# Handy_sense_v_1_0_0.net
KiCad netlist of a schematic drawn in EAGLE
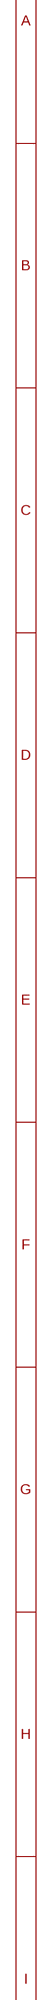
[diagram p0: schematic, sheet 1, part 1 of 2]
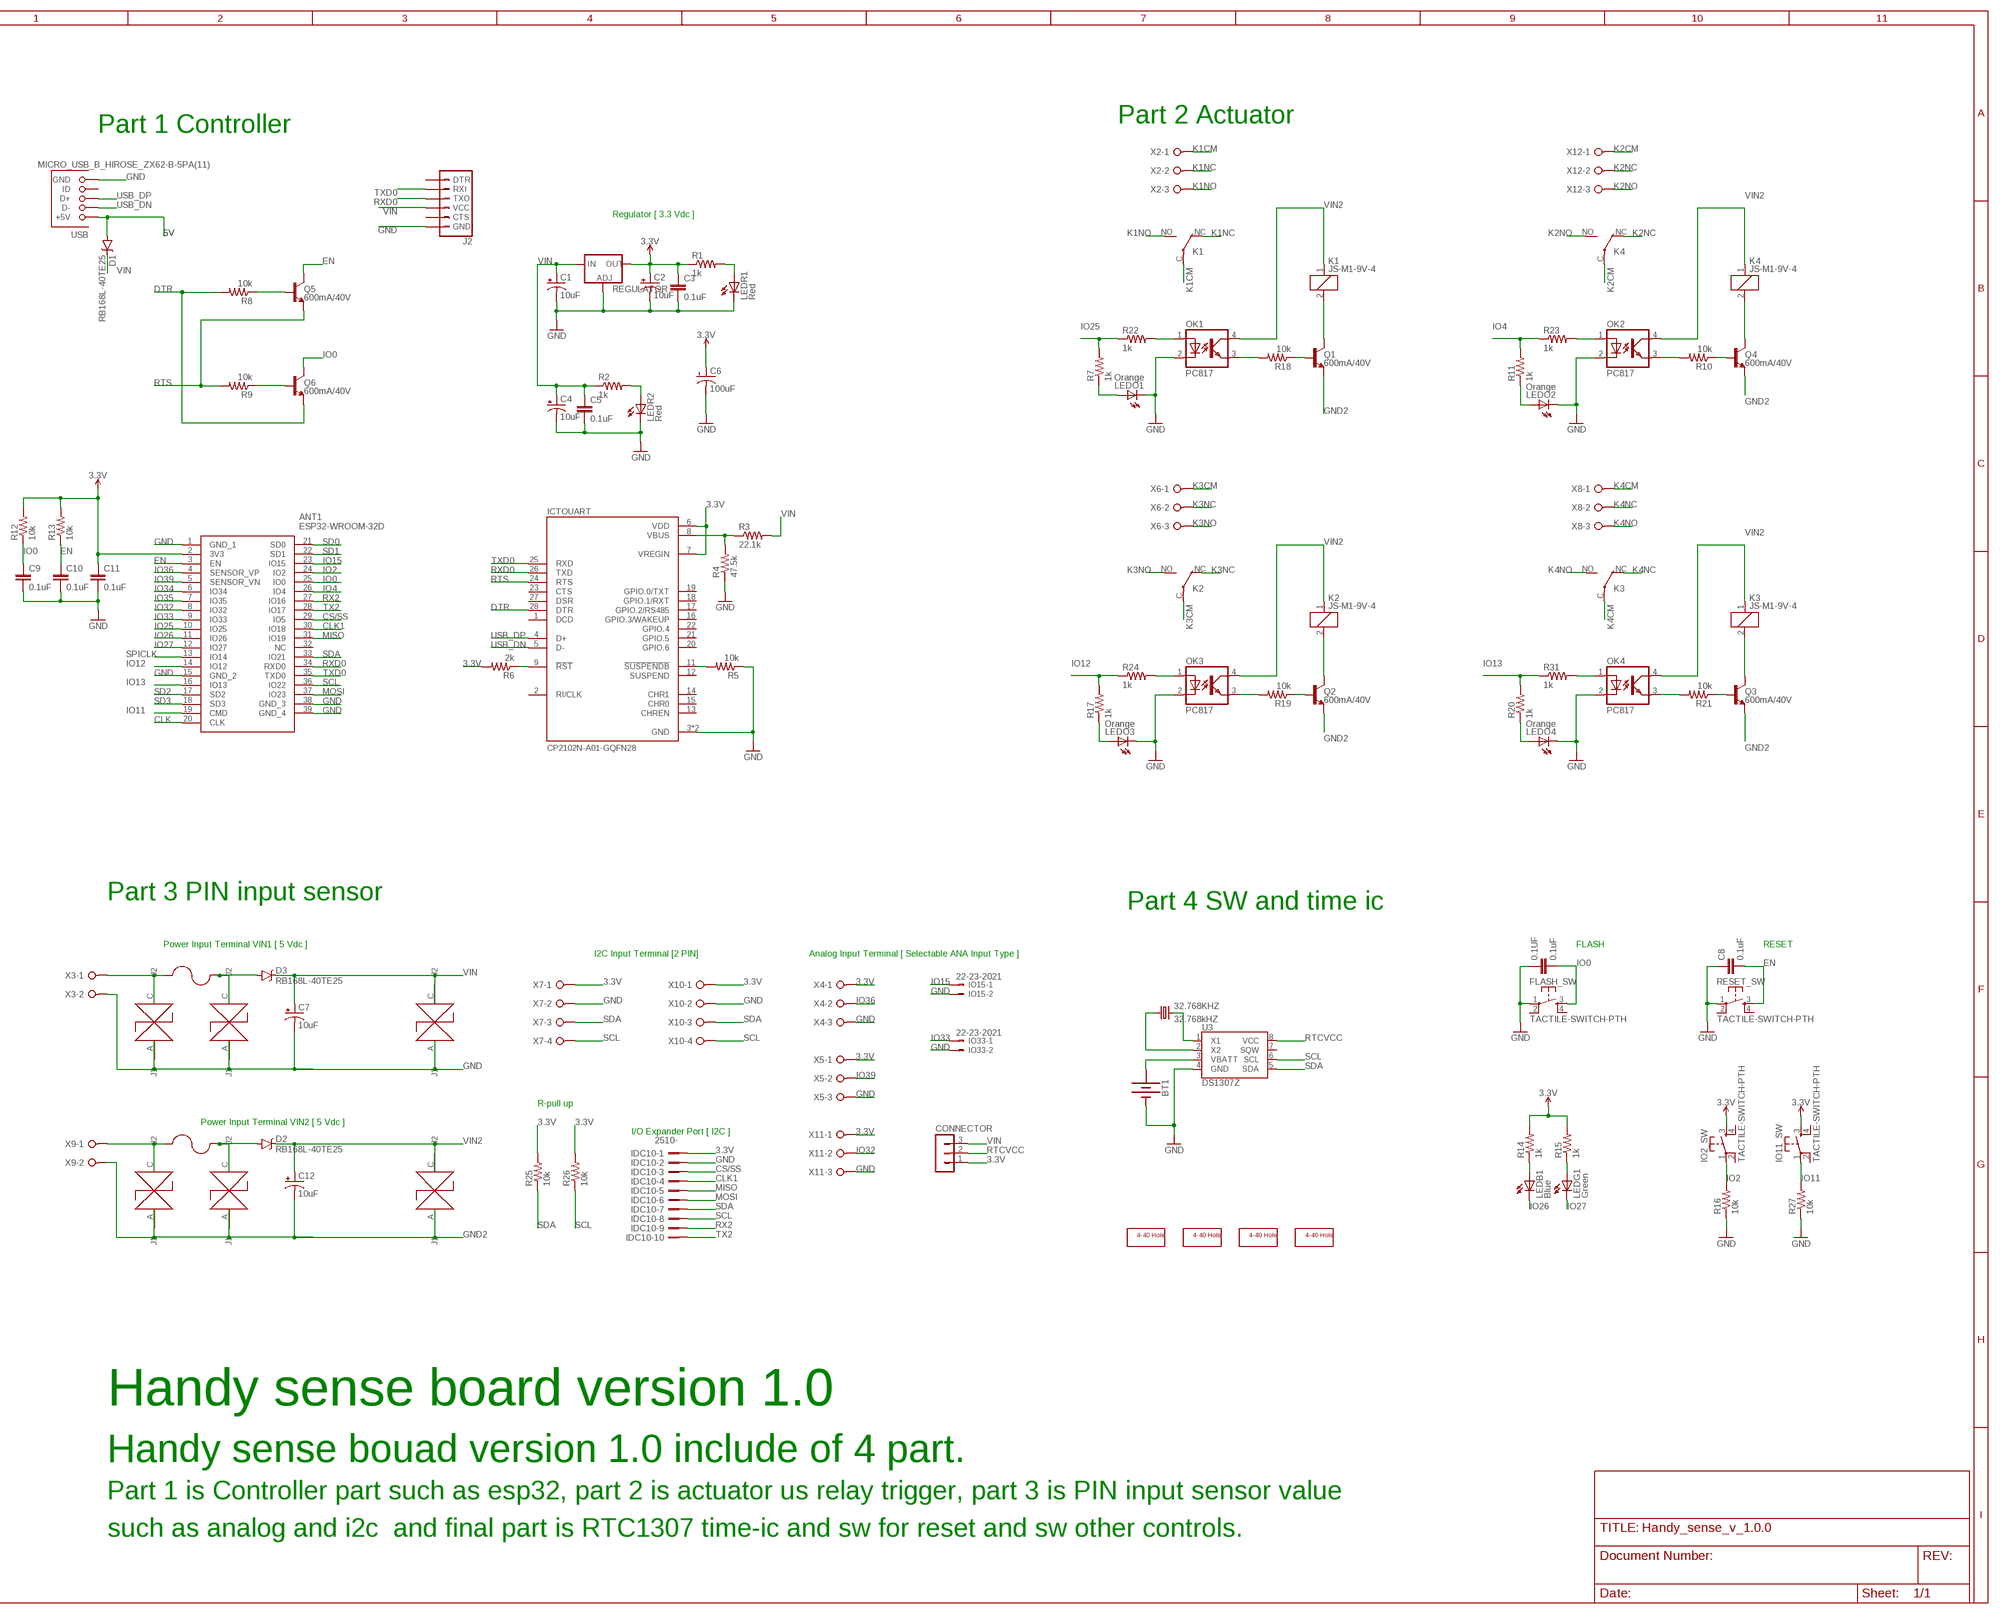
[diagram p1: schematic, sheet 1, part 2 of 2]

(export (version "E")
  (design (tool "Eeschema 10.0.6"))
  (components
    (comp (ref "0.1UF")
      (value "0.1uF")
      (footprint "eagle-import:0805")
      (libsource (lib "eagle-import") (part "CAP0805"))
    )
    (comp (ref "32.768KHZ")
      (value "32.768kHZ")
      (footprint "eagle-import:TC26H")
      (libsource (lib "eagle-import") (part "CRYSTALTC26H"))
    )
    (comp (ref "ANT1")
      (value "ESP32-WROOM-32D")
      (footprint "eagle-import:ESP32WROOM32D")
      (fields (field (name "MOUSER_PART_NUMBER") "356-ESP32WROOM-32D"))
      (libsource (lib "eagle-import") (part "ESP32-WROOM-32D"))
    )
    (comp (ref "BT1")
      (value "BATTERY-20MM_PTH_KIT")
      (footprint "eagle-import:BATTCOM_20MM_PTH_KIT")
      (libsource (lib "eagle-import") (part "BATTERY-20MM_PTH_KIT"))
    )
    (comp (ref "C1")
      (value "10uF")
      (footprint "eagle-import:EIA3216")
      (libsource (lib "eagle-import") (part "10UF-16V-10%(TANT)"))
    )
    (comp (ref "C2")
      (value "10uF")
      (footprint "eagle-import:EIA3216")
      (libsource (lib "eagle-import") (part "10UF-16V-10%(TANT)"))
    )
    (comp (ref "C3")
      (value "0.1uF")
      (footprint "eagle-import:0805")
      (libsource (lib "eagle-import") (part "CAP0805"))
    )
    (comp (ref "C4")
      (value "10uF")
      (footprint "eagle-import:EIA3216")
      (libsource (lib "eagle-import") (part "10UF-16V-10%(TANT)"))
    )
    (comp (ref "C5")
      (value "0.1uF")
      (footprint "eagle-import:0805")
      (libsource (lib "eagle-import") (part "CAP0805"))
    )
    (comp (ref "C6")
      (value "100uF")
      (footprint "eagle-import:EIA7343")
      (libsource (lib "eagle-import") (part "100UF-POLAR-EIA7343-16V-10%(TANT)"))
    )
    (comp (ref "C7")
      (value "10uF")
      (footprint "eagle-import:EIA3216")
      (libsource (lib "eagle-import") (part "10UF-16V-10%(TANT)"))
    )
    (comp (ref "C8")
      (value "0.1uF")
      (footprint "eagle-import:0805")
      (libsource (lib "eagle-import") (part "CAP0805"))
    )
    (comp (ref "C9")
      (value "0.1uF")
      (footprint "eagle-import:0805")
      (libsource (lib "eagle-import") (part "CAP0805"))
    )
    (comp (ref "C10")
      (value "0.1uF")
      (footprint "eagle-import:0805")
      (libsource (lib "eagle-import") (part "CAP0805"))
    )
    (comp (ref "C11")
      (value "0.1uF")
      (footprint "eagle-import:0805")
      (libsource (lib "eagle-import") (part "CAP0805"))
    )
    (comp (ref "C12")
      (value "10uF")
      (footprint "eagle-import:EIA3216")
      (libsource (lib "eagle-import") (part "10UF-16V-10%(TANT)"))
    )
    (comp (ref "CONNECTOR")
      (value "MA03-1")
      (footprint "eagle-import:MA03-1")
      (libsource (lib "eagle-import") (part "MA03-1"))
    )
    (comp (ref "D1")
      (value "RB168L-40TE25")
      (footprint "eagle-import:SMA-DIODE")
      (libsource (lib "eagle-import") (part "DIODE-SCHOTTKY-MBRA140"))
    )
    (comp (ref "D2")
      (value "RB168L-40TE25")
      (footprint "eagle-import:SMA-DIODE")
      (libsource (lib "eagle-import") (part "DIODE-SCHOTTKY-MBRA140"))
    )
    (comp (ref "D3")
      (value "RB168L-40TE25")
      (footprint "eagle-import:SMA-DIODE")
      (libsource (lib "eagle-import") (part "DIODE-SCHOTTKY-MBRA140"))
    )
    (comp (ref "FLASH_SW")
      (value "TACTILE-SWITCH-PTH")
      (footprint "eagle-import:TAC-SWITCH-PTH")
      (libsource (lib "eagle-import") (part "TACTILE-SWITCH-PTH"))
    )
    (comp (ref "HOLE0")
      (value "SCREW_HOLE_4-40")
      (footprint "eagle-import:SCREW_HOLE_4-40")
      (libsource (lib "eagle-import") (part "SCREW_HOLE_4-40"))
    )
    (comp (ref "HOLE1")
      (value "SCREW_HOLE_4-40")
      (footprint "eagle-import:SCREW_HOLE_4-40")
      (libsource (lib "eagle-import") (part "SCREW_HOLE_4-40"))
    )
    (comp (ref "HOLE2")
      (value "SCREW_HOLE_4-40")
      (footprint "eagle-import:SCREW_HOLE_4-40")
      (libsource (lib "eagle-import") (part "SCREW_HOLE_4-40"))
    )
    (comp (ref "HOLE3")
      (value "SCREW_HOLE_4-40")
      (footprint "eagle-import:SCREW_HOLE_4-40")
      (libsource (lib "eagle-import") (part "SCREW_HOLE_4-40"))
    )
    (comp (ref "ICTOUART")
      (value "CP2102N-A01-GQFN28")
      (footprint "eagle-import:QFN50P500X500X80-29N")
      (fields (field (name "MF") "Silicon Labs"))
      (libsource (lib "eagle-import") (part "CP2102N-A01-GQFN28"))
    )
    (comp (ref "IDC10")
      (value "2510-")
      (footprint "eagle-import:PAK100_2500-10")
      (fields (field (name "MF") "3M") (field (name "MPN") "2510-6002UB"))
      (libsource (lib "eagle-import") (part "2510-"))
    )
    (comp (ref "IO2_SW")
      (value "TACTILE-SWITCH-PTH")
      (footprint "eagle-import:TAC-SWITCH-PTH")
      (libsource (lib "eagle-import") (part "TACTILE-SWITCH-PTH"))
    )
    (comp (ref "IO11_SW")
      (value "TACTILE-SWITCH-PTH")
      (footprint "eagle-import:TAC-SWITCH-PTH")
      (libsource (lib "eagle-import") (part "TACTILE-SWITCH-PTH"))
    )
    (comp (ref "IO15")
      (value "22-23-2021")
      (footprint "eagle-import:22-23-2021")
      (fields (field (name "MF") "MOLEX"))
      (libsource (lib "eagle-import") (part "22-23-2021"))
    )
    (comp (ref "IO33")
      (value "22-23-2021")
      (footprint "eagle-import:22-23-2021")
      (fields (field (name "MF") "MOLEX"))
      (libsource (lib "eagle-import") (part "22-23-2021"))
    )
    (comp (ref "J2")
      (value "6_PIN_SERIAL_TARGET_SILK")
      (footprint "eagle-import:1X06")
      (libsource (lib "eagle-import") (part "6_PIN_SERIAL_TARGET_SILK"))
    )
    (comp (ref "J28CA1")
      (value "SMBJ28CA")
      (footprint "eagle-import:DIOM505270X240")
      (libsource (lib "eagle-import") (part "SMBJ28CA"))
    )
    (comp (ref "J28CA2")
      (value "SMBJ28CA")
      (footprint "eagle-import:DIOM505270X240")
      (libsource (lib "eagle-import") (part "SMBJ28CA"))
    )
    (comp (ref "J28CA3")
      (value "SMBJ28CA")
      (footprint "eagle-import:DIOM505270X240")
      (libsource (lib "eagle-import") (part "SMBJ28CA"))
    )
    (comp (ref "J28CA4")
      (value "SMBJ28CA")
      (footprint "eagle-import:DIOM505270X240")
      (libsource (lib "eagle-import") (part "SMBJ28CA"))
    )
    (comp (ref "J28CA5")
      (value "SMBJ28CA")
      (footprint "eagle-import:DIOM505270X240")
      (libsource (lib "eagle-import") (part "SMBJ28CA"))
    )
    (comp (ref "J28CA6")
      (value "SMBJ28CA")
      (footprint "eagle-import:DIOM505270X240")
      (libsource (lib "eagle-import") (part "SMBJ28CA"))
    )
    (comp (ref "K1")
      (value "JS-M1-9V-4")
      (footprint "eagle-import:JS-M")
      (libsource (lib "eagle-import") (part "JS-M1-9V-4"))
    )
    (comp (ref "K2")
      (value "JS-M1-9V-4")
      (footprint "eagle-import:JS-M")
      (libsource (lib "eagle-import") (part "JS-M1-9V-4"))
    )
    (comp (ref "K3")
      (value "JS-M1-9V-4")
      (footprint "eagle-import:JS-M")
      (libsource (lib "eagle-import") (part "JS-M1-9V-4"))
    )
    (comp (ref "K4")
      (value "JS-M1-9V-4")
      (footprint "eagle-import:JS-M")
      (libsource (lib "eagle-import") (part "JS-M1-9V-4"))
    )
    (comp (ref "LEDB1")
      (value "Blue")
      (footprint "eagle-import:CHIPLED_0805")
      (libsource (lib "eagle-import") (part "LEDCHIPLED_0805"))
    )
    (comp (ref "LEDG1")
      (value "Green")
      (footprint "eagle-import:CHIPLED_0805")
      (libsource (lib "eagle-import") (part "LEDCHIPLED_0805"))
    )
    (comp (ref "LEDO1")
      (value "Orange")
      (footprint "eagle-import:CHIPLED_0805")
      (libsource (lib "eagle-import") (part "LEDCHIPLED_0805"))
    )
    (comp (ref "LEDO2")
      (value "Orange")
      (footprint "eagle-import:CHIPLED_0805")
      (libsource (lib "eagle-import") (part "LEDCHIPLED_0805"))
    )
    (comp (ref "LEDO3")
      (value "Orange")
      (footprint "eagle-import:CHIPLED_0805")
      (libsource (lib "eagle-import") (part "LEDCHIPLED_0805"))
    )
    (comp (ref "LEDO4")
      (value "Orange")
      (footprint "eagle-import:CHIPLED_0805")
      (libsource (lib "eagle-import") (part "LEDCHIPLED_0805"))
    )
    (comp (ref "LEDR1")
      (value "Red")
      (footprint "eagle-import:CHIPLED_0805")
      (libsource (lib "eagle-import") (part "LEDCHIPLED_0805"))
    )
    (comp (ref "LEDR2")
      (value "Red")
      (footprint "eagle-import:CHIPLED_0805")
      (libsource (lib "eagle-import") (part "LEDCHIPLED_0805"))
    )
    (comp (ref "OK1")
      (value "PC817")
      (footprint "eagle-import:DIL04")
      (fields (field (name "MPN") "PC817X4J000F"))
      (libsource (lib "eagle-import") (part "PC817"))
    )
    (comp (ref "OK2")
      (value "PC817")
      (footprint "eagle-import:DIL04")
      (fields (field (name "MPN") "PC817X4J000F"))
      (libsource (lib "eagle-import") (part "PC817"))
    )
    (comp (ref "OK3")
      (value "PC817")
      (footprint "eagle-import:DIL04")
      (fields (field (name "MPN") "PC817X4J000F"))
      (libsource (lib "eagle-import") (part "PC817"))
    )
    (comp (ref "OK4")
      (value "PC817")
      (footprint "eagle-import:DIL04")
      (fields (field (name "MPN") "PC817X4J000F"))
      (libsource (lib "eagle-import") (part "PC817"))
    )
    (comp (ref "Q1")
      (value "600mA/40V")
      (footprint "eagle-import:SOT23-3")
      (libsource (lib "eagle-import") (part "TRANS_NPN-MMBT2222AL"))
    )
    (comp (ref "Q2")
      (value "600mA/40V")
      (footprint "eagle-import:SOT23-3")
      (libsource (lib "eagle-import") (part "TRANS_NPN-MMBT2222AL"))
    )
    (comp (ref "Q3")
      (value "600mA/40V")
      (footprint "eagle-import:SOT23-3")
      (libsource (lib "eagle-import") (part "TRANS_NPN-MMBT2222AL"))
    )
    (comp (ref "Q4")
      (value "600mA/40V")
      (footprint "eagle-import:SOT23-3")
      (libsource (lib "eagle-import") (part "TRANS_NPN-MMBT2222AL"))
    )
    (comp (ref "Q5")
      (value "600mA/40V")
      (footprint "eagle-import:SOT23-3")
      (libsource (lib "eagle-import") (part "TRANS_NPN-MMBT2222AL"))
    )
    (comp (ref "Q6")
      (value "600mA/40V")
      (footprint "eagle-import:SOT23-3")
      (libsource (lib "eagle-import") (part "TRANS_NPN-MMBT2222AL"))
    )
    (comp (ref "R1")
      (value "1k")
      (footprint "eagle-import:R0805")
      (libsource (lib "eagle-import") (part "R-US_R0805"))
    )
    (comp (ref "R2")
      (value "1k")
      (footprint "eagle-import:R0805")
      (libsource (lib "eagle-import") (part "R-US_R0805"))
    )
    (comp (ref "R3")
      (value "22.1k")
      (footprint "eagle-import:R0805")
      (libsource (lib "eagle-import") (part "R-US_R0805"))
    )
    (comp (ref "R4")
      (value "47.5k")
      (footprint "eagle-import:R0805")
      (libsource (lib "eagle-import") (part "R-US_R0805"))
    )
    (comp (ref "R5")
      (value "10k")
      (footprint "eagle-import:R0805")
      (libsource (lib "eagle-import") (part "R-US_R0805"))
    )
    (comp (ref "R6")
      (value "2k")
      (footprint "eagle-import:R0805")
      (libsource (lib "eagle-import") (part "R-US_R0805"))
    )
    (comp (ref "R7")
      (value "1k")
      (footprint "eagle-import:R0805")
      (libsource (lib "eagle-import") (part "R-US_R0805"))
    )
    (comp (ref "R8")
      (value "10k")
      (footprint "eagle-import:R0805")
      (libsource (lib "eagle-import") (part "R-US_R0805"))
    )
    (comp (ref "R9")
      (value "10k")
      (footprint "eagle-import:R0805")
      (libsource (lib "eagle-import") (part "R-US_R0805"))
    )
    (comp (ref "R10")
      (value "10k")
      (footprint "eagle-import:R0805")
      (libsource (lib "eagle-import") (part "R-US_R0805"))
    )
    (comp (ref "R11")
      (value "1k")
      (footprint "eagle-import:R0805")
      (libsource (lib "eagle-import") (part "R-US_R0805"))
    )
    (comp (ref "R12")
      (value "10k")
      (footprint "eagle-import:R0805")
      (libsource (lib "eagle-import") (part "R-US_R0805"))
    )
    (comp (ref "R13")
      (value "10k")
      (footprint "eagle-import:R0805")
      (libsource (lib "eagle-import") (part "R-US_R0805"))
    )
    (comp (ref "R14")
      (value "1k")
      (footprint "eagle-import:R0805")
      (libsource (lib "eagle-import") (part "R-US_R0805"))
    )
    (comp (ref "R15")
      (value "1k")
      (footprint "eagle-import:R0805")
      (libsource (lib "eagle-import") (part "R-US_R0805"))
    )
    (comp (ref "R16")
      (value "10k")
      (footprint "eagle-import:R0805")
      (libsource (lib "eagle-import") (part "R-US_R0805"))
    )
    (comp (ref "R17")
      (value "1k")
      (footprint "eagle-import:R0805")
      (libsource (lib "eagle-import") (part "R-US_R0805"))
    )
    (comp (ref "R18")
      (value "10k")
      (footprint "eagle-import:R0805")
      (libsource (lib "eagle-import") (part "R-US_R0805"))
    )
    (comp (ref "R19")
      (value "10k")
      (footprint "eagle-import:R0805")
      (libsource (lib "eagle-import") (part "R-US_R0805"))
    )
    (comp (ref "R20")
      (value "1k")
      (footprint "eagle-import:R0805")
      (libsource (lib "eagle-import") (part "R-US_R0805"))
    )
    (comp (ref "R21")
      (value "10k")
      (footprint "eagle-import:R0805")
      (libsource (lib "eagle-import") (part "R-US_R0805"))
    )
    (comp (ref "R22")
      (value "1k")
      (footprint "eagle-import:R0805")
      (libsource (lib "eagle-import") (part "R-US_R0805"))
    )
    (comp (ref "R23")
      (value "1k")
      (footprint "eagle-import:R0805")
      (libsource (lib "eagle-import") (part "R-US_R0805"))
    )
    (comp (ref "R24")
      (value "1k")
      (footprint "eagle-import:R0805")
      (libsource (lib "eagle-import") (part "R-US_R0805"))
    )
    (comp (ref "R25")
      (value "10k")
      (footprint "eagle-import:R0805")
      (libsource (lib "eagle-import") (part "R-US_R0805"))
    )
    (comp (ref "R26")
      (value "10k")
      (footprint "eagle-import:R0805")
      (libsource (lib "eagle-import") (part "R-US_R0805"))
    )
    (comp (ref "R27")
      (value "10k")
      (footprint "eagle-import:R0805")
      (libsource (lib "eagle-import") (part "R-US_R0805"))
    )
    (comp (ref "R31")
      (value "1k")
      (footprint "eagle-import:R0805")
      (libsource (lib "eagle-import") (part "R-US_R0805"))
    )
    (comp (ref "REGULATOR")
      (value "V_REG_LM1117SOT223")
      (footprint "eagle-import:SOT223")
      (libsource (lib "eagle-import") (part "V_REG_LM1117SOT223"))
    )
    (comp (ref "RESET_SW")
      (value "TACTILE-SWITCH-PTH")
      (footprint "eagle-import:TAC-SWITCH-PTH")
      (libsource (lib "eagle-import") (part "TACTILE-SWITCH-PTH"))
    )
    (comp (ref "U$1")
      (value "MSMFF2602")
      (footprint "eagle-import:FUSE_MF-MSMF260-2")
      (libsource (lib "eagle-import") (part "MSMFF2602"))
    )
    (comp (ref "U$2")
      (value "MSMFF2602")
      (footprint "eagle-import:FUSE_MF-MSMF260-2")
      (libsource (lib "eagle-import") (part "MSMFF2602"))
    )
    (comp (ref "U3")
      (value "DS1307Z")
      (footprint "eagle-import:SO08-0.15")
      (libsource (lib "eagle-import") (part "DS1307Z"))
    )
    (comp (ref "USB")
      (value "MICRO_USB_B_HIROSE_ZX62-B-5PA(11)")
      (footprint "eagle-import:USB_MICRO_B-HIROSE-ZX62-B-5PA(11)")
      (libsource (lib "eagle-import") (part "MICRO_USB_B_HIROSE_ZX62-B-5PA(11)"))
    )
    (comp (ref "X2")
      (value "W237-03P")
      (footprint "eagle-import:W237-133")
      (libsource (lib "eagle-import") (part "W237-03P"))
    )
    (comp (ref "X3")
      (value "W237-02P")
      (footprint "eagle-import:W237-132")
      (libsource (lib "eagle-import") (part "W237-02P"))
    )
    (comp (ref "X4")
      (value "W237-03P")
      (footprint "eagle-import:W237-133")
      (libsource (lib "eagle-import") (part "W237-03P"))
    )
    (comp (ref "X5")
      (value "W237-03P")
      (footprint "eagle-import:W237-133")
      (libsource (lib "eagle-import") (part "W237-03P"))
    )
    (comp (ref "X6")
      (value "W237-03P")
      (footprint "eagle-import:W237-133")
      (libsource (lib "eagle-import") (part "W237-03P"))
    )
    (comp (ref "X7")
      (value "W237-04P")
      (footprint "eagle-import:W237-4P")
      (libsource (lib "eagle-import") (part "W237-04P"))
    )
    (comp (ref "X8")
      (value "W237-03P")
      (footprint "eagle-import:W237-133")
      (libsource (lib "eagle-import") (part "W237-03P"))
    )
    (comp (ref "X9")
      (value "W237-02P")
      (footprint "eagle-import:W237-132")
      (libsource (lib "eagle-import") (part "W237-02P"))
    )
    (comp (ref "X10")
      (value "W237-04P")
      (footprint "eagle-import:W237-4P")
      (libsource (lib "eagle-import") (part "W237-04P"))
    )
    (comp (ref "X11")
      (value "W237-03P")
      (footprint "eagle-import:W237-133")
      (libsource (lib "eagle-import") (part "W237-03P"))
    )
    (comp (ref "X12")
      (value "W237-03P")
      (footprint "eagle-import:W237-133")
      (libsource (lib "eagle-import") (part "W237-03P"))
    )
  )
  (nets
    (net (code "1") (name "/5V") (class "Default")
      (node (ref "D1") (pin "A") (pinfunction "A_A") (pintype "passive"))
      (node (ref "USB") (pin "1") (pinfunction "+5V_1") (pintype "bidirectional"))
    )
    (net (code "2") (name "/CLK") (class "Default")
      (node (ref "ANT1") (pin "20") (pinfunction "CLK_20") (pintype "bidirectional"))
    )
    (net (code "3") (name "/CLK1") (class "Default")
      (node (ref "ANT1") (pin "30") (pinfunction "IO18_30") (pintype "bidirectional"))
      (node (ref "IDC10") (pin "4") (pinfunction "KL_4") (pintype "passive"))
    )
    (net (code "4") (name "/CS{slash}SS") (class "Default")
      (node (ref "ANT1") (pin "29") (pinfunction "IO5_29") (pintype "bidirectional"))
      (node (ref "IDC10") (pin "3") (pinfunction "KL_3") (pintype "passive"))
    )
    (net (code "5") (name "/DTR") (class "Default")
      (node (ref "ICTOUART") (pin "28") (pinfunction "DTR_28") (pintype "output"))
      (node (ref "Q6") (pin "2") (pinfunction "E_2") (pintype "passive"))
      (node (ref "R8") (pin "2") (pinfunction "2_2") (pintype "passive"))
    )
    (net (code "6") (name "/EN") (class "Default")
      (node (ref "ANT1") (pin "3") (pinfunction "EN_3") (pintype "bidirectional"))
      (node (ref "C10") (pin "1") (pinfunction "1_1") (pintype "passive"))
      (node (ref "C8") (pin "2") (pinfunction "2_2") (pintype "passive"))
      (node (ref "Q5") (pin "3") (pinfunction "C_3") (pintype "passive"))
      (node (ref "R13") (pin "1") (pinfunction "1_1") (pintype "passive"))
      (node (ref "RESET_SW") (pin "3") (pinfunction "3_3") (pintype "passive"))
    )
    (net (code "7") (name "/GND2") (class "Default")
      (node (ref "C12") (pin "C") (pinfunction "-_C") (pintype "passive"))
      (node (ref "J28CA4") (pin "A") (pinfunction "J1_A") (pintype "bidirectional"))
      (node (ref "J28CA5") (pin "A") (pinfunction "J1_A") (pintype "bidirectional"))
      (node (ref "J28CA6") (pin "A") (pinfunction "J1_A") (pintype "bidirectional"))
      (node (ref "Q1") (pin "2") (pinfunction "E_2") (pintype "passive"))
      (node (ref "Q2") (pin "2") (pinfunction "E_2") (pintype "passive"))
      (node (ref "Q3") (pin "2") (pinfunction "E_2") (pintype "passive"))
      (node (ref "Q4") (pin "2") (pinfunction "E_2") (pintype "passive"))
      (node (ref "X9") (pin "2") (pinfunction "KL_2") (pintype "passive"))
    )
    (net (code "8") (name "/IO0") (class "Default")
      (node (ref "0.1UF") (pin "2") (pinfunction "2_2") (pintype "passive"))
      (node (ref "ANT1") (pin "25") (pinfunction "IO0_25") (pintype "bidirectional"))
      (node (ref "C9") (pin "1") (pinfunction "1_1") (pintype "passive"))
      (node (ref "FLASH_SW") (pin "3") (pinfunction "3_3") (pintype "passive"))
      (node (ref "Q6") (pin "3") (pinfunction "C_3") (pintype "passive"))
      (node (ref "R12") (pin "1") (pinfunction "1_1") (pintype "passive"))
    )
    (net (code "9") (name "/IO2") (class "Default")
      (node (ref "ANT1") (pin "24") (pinfunction "IO2_24") (pintype "bidirectional"))
      (node (ref "IO2_SW") (pin "1") (pinfunction "1_1") (pintype "passive"))
      (node (ref "R16") (pin "2") (pinfunction "2_2") (pintype "passive"))
    )
    (net (code "10") (name "/IO4") (class "Default")
      (node (ref "ANT1") (pin "26") (pinfunction "IO4_26") (pintype "bidirectional"))
      (node (ref "R11") (pin "2") (pinfunction "2_2") (pintype "passive"))
      (node (ref "R23") (pin "1") (pinfunction "1_1") (pintype "passive"))
    )
    (net (code "11") (name "/IO11") (class "Default")
      (node (ref "ANT1") (pin "19") (pinfunction "CMD_19") (pintype "bidirectional"))
      (node (ref "IO11_SW") (pin "1") (pinfunction "1_1") (pintype "passive"))
      (node (ref "R27") (pin "2") (pinfunction "2_2") (pintype "passive"))
    )
    (net (code "12") (name "/IO12") (class "Default")
      (node (ref "ANT1") (pin "14") (pinfunction "IO12_14") (pintype "bidirectional"))
      (node (ref "R17") (pin "2") (pinfunction "2_2") (pintype "passive"))
      (node (ref "R24") (pin "1") (pinfunction "1_1") (pintype "passive"))
    )
    (net (code "13") (name "/IO13") (class "Default")
      (node (ref "ANT1") (pin "16") (pinfunction "IO13_16") (pintype "bidirectional"))
      (node (ref "R20") (pin "2") (pinfunction "2_2") (pintype "passive"))
      (node (ref "R31") (pin "1") (pinfunction "1_1") (pintype "passive"))
    )
    (net (code "14") (name "/IO15") (class "Default")
      (node (ref "ANT1") (pin "23") (pinfunction "IO15_23") (pintype "bidirectional"))
      (node (ref "IO15") (pin "1") (pinfunction "S_1") (pintype "passive"))
    )
    (net (code "15") (name "/IO25") (class "Default")
      (node (ref "ANT1") (pin "10") (pinfunction "IO25_10") (pintype "bidirectional"))
      (node (ref "R22") (pin "1") (pinfunction "1_1") (pintype "passive"))
      (node (ref "R7") (pin "2") (pinfunction "2_2") (pintype "passive"))
    )
    (net (code "16") (name "/IO26") (class "Default")
      (node (ref "ANT1") (pin "11") (pinfunction "IO26_11") (pintype "bidirectional"))
      (node (ref "LEDB1") (pin "C") (pinfunction "C_C") (pintype "passive"))
    )
    (net (code "17") (name "/IO27") (class "Default")
      (node (ref "ANT1") (pin "12") (pinfunction "IO27_12") (pintype "bidirectional"))
      (node (ref "LEDG1") (pin "C") (pinfunction "C_C") (pintype "passive"))
    )
    (net (code "18") (name "/IO32") (class "Default")
      (node (ref "ANT1") (pin "8") (pinfunction "IO32_8") (pintype "bidirectional"))
      (node (ref "X11") (pin "2") (pinfunction "KL_2") (pintype "passive"))
    )
    (net (code "19") (name "/IO33") (class "Default")
      (node (ref "ANT1") (pin "9") (pinfunction "IO33_9") (pintype "bidirectional"))
      (node (ref "IO33") (pin "1") (pinfunction "S_1") (pintype "passive"))
    )
    (net (code "20") (name "/IO34") (class "Default")
      (node (ref "ANT1") (pin "6") (pinfunction "IO34_6") (pintype "bidirectional"))
    )
    (net (code "21") (name "/IO35") (class "Default")
      (node (ref "ANT1") (pin "7") (pinfunction "IO35_7") (pintype "bidirectional"))
    )
    (net (code "22") (name "/IO36") (class "Default")
      (node (ref "ANT1") (pin "4") (pinfunction "SENSOR_VP_4") (pintype "bidirectional"))
      (node (ref "X4") (pin "2") (pinfunction "KL_2") (pintype "passive"))
    )
    (net (code "23") (name "/IO39") (class "Default")
      (node (ref "ANT1") (pin "5") (pinfunction "SENSOR_VN_5") (pintype "bidirectional"))
      (node (ref "X5") (pin "2") (pinfunction "KL_2") (pintype "passive"))
    )
    (net (code "24") (name "/K1CM") (class "Default")
      (node (ref "K1") (pin "C") (pinfunction "P_C") (pintype "passive"))
      (node (ref "X2") (pin "1") (pinfunction "KL_1") (pintype "passive"))
    )
    (net (code "25") (name "/K1NC") (class "Default")
      (node (ref "K1") (pin "NC") (pinfunction "O_NC") (pintype "passive"))
      (node (ref "X2") (pin "2") (pinfunction "KL_2") (pintype "passive"))
    )
    (net (code "26") (name "/K1NO") (class "Default")
      (node (ref "K1") (pin "NO") (pinfunction "S_NO") (pintype "passive"))
      (node (ref "X2") (pin "3") (pinfunction "KL_3") (pintype "passive"))
    )
    (net (code "27") (name "/K2CM") (class "Default")
      (node (ref "K4") (pin "C") (pinfunction "P_C") (pintype "passive"))
      (node (ref "X12") (pin "1") (pinfunction "KL_1") (pintype "passive"))
    )
    (net (code "28") (name "/K2NC") (class "Default")
      (node (ref "K4") (pin "NC") (pinfunction "O_NC") (pintype "passive"))
      (node (ref "X12") (pin "2") (pinfunction "KL_2") (pintype "passive"))
    )
    (net (code "29") (name "/K2NO") (class "Default")
      (node (ref "K4") (pin "NO") (pinfunction "S_NO") (pintype "passive"))
      (node (ref "X12") (pin "3") (pinfunction "KL_3") (pintype "passive"))
    )
    (net (code "30") (name "/K3CM") (class "Default")
      (node (ref "K2") (pin "C") (pinfunction "P_C") (pintype "passive"))
      (node (ref "X6") (pin "1") (pinfunction "KL_1") (pintype "passive"))
    )
    (net (code "31") (name "/K3NC") (class "Default")
      (node (ref "K2") (pin "NC") (pinfunction "O_NC") (pintype "passive"))
      (node (ref "X6") (pin "2") (pinfunction "KL_2") (pintype "passive"))
    )
    (net (code "32") (name "/K3NO") (class "Default")
      (node (ref "K2") (pin "NO") (pinfunction "S_NO") (pintype "passive"))
      (node (ref "X6") (pin "3") (pinfunction "KL_3") (pintype "passive"))
    )
    (net (code "33") (name "/K4CM") (class "Default")
      (node (ref "K3") (pin "C") (pinfunction "P_C") (pintype "passive"))
      (node (ref "X8") (pin "1") (pinfunction "KL_1") (pintype "passive"))
    )
    (net (code "34") (name "/K4NC") (class "Default")
      (node (ref "K3") (pin "NC") (pinfunction "O_NC") (pintype "passive"))
      (node (ref "X8") (pin "2") (pinfunction "KL_2") (pintype "passive"))
    )
    (net (code "35") (name "/K4NO") (class "Default")
      (node (ref "K3") (pin "NO") (pinfunction "S_NO") (pintype "passive"))
      (node (ref "X8") (pin "3") (pinfunction "KL_3") (pintype "passive"))
    )
    (net (code "36") (name "/MISO") (class "Default")
      (node (ref "ANT1") (pin "31") (pinfunction "IO19_31") (pintype "bidirectional"))
      (node (ref "IDC10") (pin "5") (pinfunction "KL_5") (pintype "passive"))
    )
    (net (code "37") (name "/MOSI") (class "Default")
      (node (ref "ANT1") (pin "37") (pinfunction "IO23_37") (pintype "bidirectional"))
      (node (ref "IDC10") (pin "6") (pinfunction "KL_6") (pintype "passive"))
    )
    (net (code "38") (name "/RTCVCC") (class "Default")
      (node (ref "CONNECTOR") (pin "2") (pinfunction "2_2") (pintype "passive"))
      (node (ref "U3") (pin "8") (pinfunction "VCC_8") (pintype "bidirectional"))
    )
    (net (code "39") (name "/RTS") (class "Default")
      (node (ref "ICTOUART") (pin "24") (pinfunction "RTS_24") (pintype "output"))
      (node (ref "Q5") (pin "2") (pinfunction "E_2") (pintype "passive"))
      (node (ref "R9") (pin "2") (pinfunction "2_2") (pintype "passive"))
    )
    (net (code "40") (name "/RX2") (class "Default")
      (node (ref "ANT1") (pin "27") (pinfunction "IO16_27") (pintype "bidirectional"))
      (node (ref "IDC10") (pin "9") (pinfunction "KL_9") (pintype "passive"))
    )
    (net (code "41") (name "/RXD0") (class "Default")
      (node (ref "ANT1") (pin "34") (pinfunction "RXD0_34") (pintype "bidirectional"))
      (node (ref "ICTOUART") (pin "26") (pinfunction "TXD_26") (pintype "output"))
      (node (ref "J2") (pin "3") (pinfunction "TXO_3") (pintype "passive"))
    )
    (net (code "42") (name "/SCL") (class "Default")
      (node (ref "ANT1") (pin "36") (pinfunction "IO22_36") (pintype "bidirectional"))
      (node (ref "IDC10") (pin "8") (pinfunction "KL_8") (pintype "passive"))
      (node (ref "R26") (pin "1") (pinfunction "1_1") (pintype "passive"))
      (node (ref "U3") (pin "6") (pinfunction "SCL_6") (pintype "bidirectional"))
      (node (ref "X10") (pin "4") (pinfunction "KL_4") (pintype "passive"))
      (node (ref "X7") (pin "4") (pinfunction "KL_4") (pintype "passive"))
    )
    (net (code "43") (name "/SD0") (class "Default")
      (node (ref "ANT1") (pin "21") (pinfunction "SD0_21") (pintype "bidirectional"))
    )
    (net (code "44") (name "/SD1") (class "Default")
      (node (ref "ANT1") (pin "22") (pinfunction "SD1_22") (pintype "bidirectional"))
    )
    (net (code "45") (name "/SD2") (class "Default")
      (node (ref "ANT1") (pin "17") (pinfunction "SD2_17") (pintype "bidirectional"))
    )
    (net (code "46") (name "/SD3") (class "Default")
      (node (ref "ANT1") (pin "18") (pinfunction "SD3_18") (pintype "bidirectional"))
    )
    (net (code "47") (name "/SDA") (class "Default")
      (node (ref "ANT1") (pin "33") (pinfunction "IO21_33") (pintype "bidirectional"))
      (node (ref "IDC10") (pin "7") (pinfunction "KL_7") (pintype "passive"))
      (node (ref "R25") (pin "1") (pinfunction "1_1") (pintype "passive"))
      (node (ref "U3") (pin "5") (pinfunction "SDA_5") (pintype "bidirectional"))
      (node (ref "X10") (pin "3") (pinfunction "KL_3") (pintype "passive"))
      (node (ref "X7") (pin "3") (pinfunction "KL_3") (pintype "passive"))
    )
    (net (code "48") (name "/SPICLK") (class "Default")
      (node (ref "ANT1") (pin "13") (pinfunction "IO14_13") (pintype "bidirectional"))
    )
    (net (code "49") (name "/TX2") (class "Default")
      (node (ref "ANT1") (pin "28") (pinfunction "IO17_28") (pintype "bidirectional"))
      (node (ref "IDC10") (pin "10") (pinfunction "KL_10") (pintype "passive"))
    )
    (net (code "50") (name "/TXD0") (class "Default")
      (node (ref "ANT1") (pin "35") (pinfunction "TXD0_35") (pintype "bidirectional"))
      (node (ref "ICTOUART") (pin "25") (pinfunction "RXD_25") (pintype "input"))
      (node (ref "J2") (pin "2") (pinfunction "RXI_2") (pintype "passive"))
    )
    (net (code "51") (name "/USB_DN") (class "Default")
      (node (ref "ICTOUART") (pin "5") (pinfunction "D-_5") (pintype "bidirectional"))
      (node (ref "USB") (pin "2") (pinfunction "D-_2") (pintype "bidirectional"))
    )
    (net (code "52") (name "/USB_DP") (class "Default")
      (node (ref "ICTOUART") (pin "4") (pinfunction "D+_4") (pintype "bidirectional"))
      (node (ref "USB") (pin "3") (pinfunction "D+_3") (pintype "bidirectional"))
    )
    (net (code "53") (name "/VIN") (class "Default")
      (node (ref "C1") (pin "A") (pinfunction "+_A") (pintype "passive"))
      (node (ref "C4") (pin "A") (pinfunction "+_A") (pintype "passive"))
      (node (ref "C5") (pin "1") (pinfunction "1_1") (pintype "passive"))
      (node (ref "C7") (pin "A") (pinfunction "+_A") (pintype "passive"))
      (node (ref "CONNECTOR") (pin "3") (pinfunction "3_3") (pintype "passive"))
      (node (ref "D1") (pin "C") (pinfunction "C_C") (pintype "passive"))
      (node (ref "D3") (pin "C") (pinfunction "C_C") (pintype "passive"))
      (node (ref "J2") (pin "4") (pinfunction "VCC_4") (pintype "passive"))
      (node (ref "J28CA3") (pin "C") (pinfunction "J2_C") (pintype "bidirectional"))
      (node (ref "R2") (pin "1") (pinfunction "1_1") (pintype "passive"))
      (node (ref "R3") (pin "2") (pinfunction "2_2") (pintype "passive"))
      (node (ref "REGULATOR") (pin "3") (pinfunction "IN_3") (pintype "input"))
    )
    (net (code "54") (name "/VIN2") (class "Default")
      (node (ref "C12") (pin "A") (pinfunction "+_A") (pintype "passive"))
      (node (ref "D2") (pin "C") (pinfunction "C_C") (pintype "passive"))
      (node (ref "J28CA6") (pin "C") (pinfunction "J2_C") (pintype "bidirectional"))
      (node (ref "K1") (pin "1") (pinfunction "1_1") (pintype "passive"))
      (node (ref "K2") (pin "1") (pinfunction "1_1") (pintype "passive"))
      (node (ref "K3") (pin "1") (pinfunction "1_1") (pintype "passive"))
      (node (ref "K4") (pin "1") (pinfunction "1_1") (pintype "passive"))
      (node (ref "OK1") (pin "4") (pinfunction "COL_4") (pintype "passive"))
      (node (ref "OK2") (pin "4") (pinfunction "COL_4") (pintype "passive"))
      (node (ref "OK3") (pin "4") (pinfunction "COL_4") (pintype "passive"))
      (node (ref "OK4") (pin "4") (pinfunction "COL_4") (pintype "passive"))
    )
    (net (code "55") (name "3.3V") (class "Default")
      (node (ref "ANT1") (pin "2") (pinfunction "3V3_2") (pintype "bidirectional"))
      (node (ref "C11") (pin "1") (pinfunction "1_1") (pintype "passive"))
      (node (ref "C2") (pin "A") (pinfunction "+_A") (pintype "passive"))
      (node (ref "C3") (pin "1") (pinfunction "1_1") (pintype "passive"))
      (node (ref "C6") (pin "A") (pinfunction "+_A") (pintype "passive"))
      (node (ref "CONNECTOR") (pin "1") (pinfunction "1_1") (pintype "passive"))
      (node (ref "ICTOUART") (pin "6") (pinfunction "VDD_6") (pintype "power_in"))
      (node (ref "ICTOUART") (pin "7") (pinfunction "VREGIN_7") (pintype "power_in"))
      (node (ref "IDC10") (pin "1") (pinfunction "KL_1") (pintype "passive"))
      (node (ref "IO11_SW") (pin "3") (pinfunction "3_3") (pintype "passive"))
      (node (ref "IO2_SW") (pin "3") (pinfunction "3_3") (pintype "passive"))
      (node (ref "R1") (pin "1") (pinfunction "1_1") (pintype "passive"))
      (node (ref "R12") (pin "2") (pinfunction "2_2") (pintype "passive"))
      (node (ref "R13") (pin "2") (pinfunction "2_2") (pintype "passive"))
      (node (ref "R14") (pin "2") (pinfunction "2_2") (pintype "passive"))
      (node (ref "R15") (pin "2") (pinfunction "2_2") (pintype "passive"))
      (node (ref "R25") (pin "2") (pinfunction "2_2") (pintype "passive"))
      (node (ref "R26") (pin "2") (pinfunction "2_2") (pintype "passive"))
      (node (ref "R6") (pin "2") (pinfunction "2_2") (pintype "passive"))
      (node (ref "REGULATOR") (pin "2") (pinfunction "OUT_2") (pintype "output"))
      (node (ref "REGULATOR") (pin "4") (pinfunction "OUT_4") (pintype "output"))
      (node (ref "X10") (pin "1") (pinfunction "KL_1") (pintype "passive"))
      (node (ref "X11") (pin "1") (pinfunction "KL_1") (pintype "passive"))
      (node (ref "X4") (pin "1") (pinfunction "KL_1") (pintype "passive"))
      (node (ref "X5") (pin "1") (pinfunction "KL_1") (pintype "passive"))
      (node (ref "X7") (pin "1") (pinfunction "KL_1") (pintype "passive"))
    )
    (net (code "56") (name "GND") (class "Default")
      (node (ref "0.1UF") (pin "1") (pinfunction "1_1") (pintype "passive"))
      (node (ref "ANT1") (pin "1") (pinfunction "GND_1_1") (pintype "bidirectional"))
      (node (ref "ANT1") (pin "15") (pinfunction "GND_2_15") (pintype "bidirectional"))
      (node (ref "ANT1") (pin "38") (pinfunction "GND_3_38") (pintype "bidirectional"))
      (node (ref "ANT1") (pin "39") (pinfunction "GND_4_39") (pintype "bidirectional"))
      (node (ref "BT1") (pin "2") (pinfunction "-_2") (pintype "power_in"))
      (node (ref "C1") (pin "C") (pinfunction "-_C") (pintype "passive"))
      (node (ref "C10") (pin "2") (pinfunction "2_2") (pintype "passive"))
      (node (ref "C11") (pin "2") (pinfunction "2_2") (pintype "passive"))
      (node (ref "C2") (pin "C") (pinfunction "-_C") (pintype "passive"))
      (node (ref "C3") (pin "2") (pinfunction "2_2") (pintype "passive"))
      (node (ref "C4") (pin "C") (pinfunction "-_C") (pintype "passive"))
      (node (ref "C5") (pin "2") (pinfunction "2_2") (pintype "passive"))
      (node (ref "C6") (pin "C") (pinfunction "-_C") (pintype "passive"))
      (node (ref "C7") (pin "C") (pinfunction "-_C") (pintype "passive"))
      (node (ref "C8") (pin "1") (pinfunction "1_1") (pintype "passive"))
      (node (ref "C9") (pin "2") (pinfunction "2_2") (pintype "passive"))
      (node (ref "FLASH_SW") (pin "1") (pinfunction "1_1") (pintype "passive"))
      (node (ref "ICTOUART") (pin "29") (pinfunction "GND_29") (pintype "power_in"))
      (node (ref "ICTOUART") (pin "3") (pinfunction "GND_3") (pintype "power_in"))
      (node (ref "IDC10") (pin "2") (pinfunction "KL_2") (pintype "passive"))
      (node (ref "IO15") (pin "2") (pinfunction "S_2") (pintype "passive"))
      (node (ref "IO33") (pin "2") (pinfunction "S_2") (pintype "passive"))
      (node (ref "J2") (pin "6") (pinfunction "GND_6") (pintype "passive"))
      (node (ref "J28CA1") (pin "A") (pinfunction "J1_A") (pintype "bidirectional"))
      (node (ref "J28CA2") (pin "A") (pinfunction "J1_A") (pintype "bidirectional"))
      (node (ref "J28CA3") (pin "A") (pinfunction "J1_A") (pintype "bidirectional"))
      (node (ref "LEDO1") (pin "C") (pinfunction "C_C") (pintype "passive"))
      (node (ref "LEDO2") (pin "C") (pinfunction "C_C") (pintype "passive"))
      (node (ref "LEDO3") (pin "C") (pinfunction "C_C") (pintype "passive"))
      (node (ref "LEDO4") (pin "C") (pinfunction "C_C") (pintype "passive"))
      (node (ref "LEDR1") (pin "C") (pinfunction "C_C") (pintype "passive"))
      (node (ref "LEDR2") (pin "C") (pinfunction "C_C") (pintype "passive"))
      (node (ref "OK1") (pin "2") (pinfunction "C_2") (pintype "passive"))
      (node (ref "OK2") (pin "2") (pinfunction "C_2") (pintype "passive"))
      (node (ref "OK3") (pin "2") (pinfunction "C_2") (pintype "passive"))
      (node (ref "OK4") (pin "2") (pinfunction "C_2") (pintype "passive"))
      (node (ref "R16") (pin "1") (pinfunction "1_1") (pintype "passive"))
      (node (ref "R27") (pin "1") (pinfunction "1_1") (pintype "passive"))
      (node (ref "R4") (pin "1") (pinfunction "1_1") (pintype "passive"))
      (node (ref "R5") (pin "1") (pinfunction "1_1") (pintype "passive"))
      (node (ref "REGULATOR") (pin "1") (pinfunction "ADJ_1") (pintype "input"))
      (node (ref "RESET_SW") (pin "1") (pinfunction "1_1") (pintype "passive"))
      (node (ref "U3") (pin "4") (pinfunction "GND_4") (pintype "bidirectional"))
      (node (ref "USB") (pin "5") (pinfunction "GND_5") (pintype "bidirectional"))
      (node (ref "X10") (pin "2") (pinfunction "KL_2") (pintype "passive"))
      (node (ref "X11") (pin "3") (pinfunction "KL_3") (pintype "passive"))
      (node (ref "X3") (pin "2") (pinfunction "KL_2") (pintype "passive"))
      (node (ref "X4") (pin "3") (pinfunction "KL_3") (pintype "passive"))
      (node (ref "X5") (pin "3") (pinfunction "KL_3") (pintype "passive"))
      (node (ref "X7") (pin "2") (pinfunction "KL_2") (pintype "passive"))
    )
    (net (code "57") (name "Net-(BT1-+)") (class "Default")
      (node (ref "BT1") (pin "1") (pinfunction "+_1") (pintype "power_in"))
      (node (ref "U3") (pin "3") (pinfunction "VBATT_3") (pintype "bidirectional"))
    )
    (net (code "58") (name "Net-(ICTOUART-VBUS)") (class "Default")
      (node (ref "ICTOUART") (pin "8") (pinfunction "VBUS_8") (pintype "power_in"))
      (node (ref "R3") (pin "1") (pinfunction "1_1") (pintype "passive"))
      (node (ref "R4") (pin "2") (pinfunction "2_2") (pintype "passive"))
    )
    (net (code "59") (name "Net-(ICTOUART-~{RST})") (class "Default")
      (node (ref "ICTOUART") (pin "9") (pinfunction "~{RST}_9") (pintype "input"))
      (node (ref "R6") (pin "1") (pinfunction "1_1") (pintype "passive"))
    )
    (net (code "60") (name "Net-(ICTOUART-~{SUSPENDB})") (class "Default")
      (node (ref "ICTOUART") (pin "11") (pinfunction "~{SUSPENDB}_11") (pintype "output"))
      (node (ref "R5") (pin "2") (pinfunction "2_2") (pintype "passive"))
    )
    (net (code "61") (name "Net-(J28CA1-J2)") (class "Default")
      (node (ref "J28CA1") (pin "C") (pinfunction "J2_C") (pintype "bidirectional"))
      (node (ref "U$1") (pin "1") (pinfunction "P1_1") (pintype "input"))
      (node (ref "X3") (pin "1") (pinfunction "KL_1") (pintype "passive"))
    )
    (net (code "62") (name "Net-(J28CA2-J2)") (class "Default")
      (node (ref "D3") (pin "A") (pinfunction "A_A") (pintype "passive"))
      (node (ref "J28CA2") (pin "C") (pinfunction "J2_C") (pintype "bidirectional"))
      (node (ref "U$1") (pin "2") (pinfunction "P$2_2") (pintype "output"))
    )
    (net (code "63") (name "Net-(J28CA4-J2)") (class "Default")
      (node (ref "J28CA4") (pin "C") (pinfunction "J2_C") (pintype "bidirectional"))
      (node (ref "U$2") (pin "1") (pinfunction "P1_1") (pintype "input"))
      (node (ref "X9") (pin "1") (pinfunction "KL_1") (pintype "passive"))
    )
    (net (code "64") (name "Net-(J28CA5-J2)") (class "Default")
      (node (ref "D2") (pin "A") (pinfunction "A_A") (pintype "passive"))
      (node (ref "J28CA5") (pin "C") (pinfunction "J2_C") (pintype "bidirectional"))
      (node (ref "U$2") (pin "2") (pinfunction "P$2_2") (pintype "output"))
    )
    (net (code "65") (name "Net-(LEDB1-PadA)") (class "Default")
      (node (ref "LEDB1") (pin "A") (pinfunction "A_A") (pintype "passive"))
      (node (ref "R14") (pin "1") (pinfunction "1_1") (pintype "passive"))
    )
    (net (code "66") (name "Net-(LEDG1-PadA)") (class "Default")
      (node (ref "LEDG1") (pin "A") (pinfunction "A_A") (pintype "passive"))
      (node (ref "R15") (pin "1") (pinfunction "1_1") (pintype "passive"))
    )
    (net (code "67") (name "Net-(LEDO1-PadA)") (class "Default")
      (node (ref "LEDO1") (pin "A") (pinfunction "A_A") (pintype "passive"))
      (node (ref "R7") (pin "1") (pinfunction "1_1") (pintype "passive"))
    )
    (net (code "68") (name "Net-(LEDO2-PadA)") (class "Default")
      (node (ref "LEDO2") (pin "A") (pinfunction "A_A") (pintype "passive"))
      (node (ref "R11") (pin "1") (pinfunction "1_1") (pintype "passive"))
    )
    (net (code "69") (name "Net-(LEDO3-PadA)") (class "Default")
      (node (ref "LEDO3") (pin "A") (pinfunction "A_A") (pintype "passive"))
      (node (ref "R17") (pin "1") (pinfunction "1_1") (pintype "passive"))
    )
    (net (code "70") (name "Net-(LEDO4-PadA)") (class "Default")
      (node (ref "LEDO4") (pin "A") (pinfunction "A_A") (pintype "passive"))
      (node (ref "R20") (pin "1") (pinfunction "1_1") (pintype "passive"))
    )
    (net (code "71") (name "Net-(LEDR1-PadA)") (class "Default")
      (node (ref "LEDR1") (pin "A") (pinfunction "A_A") (pintype "passive"))
      (node (ref "R1") (pin "2") (pinfunction "2_2") (pintype "passive"))
    )
    (net (code "72") (name "Net-(LEDR2-PadA)") (class "Default")
      (node (ref "LEDR2") (pin "A") (pinfunction "A_A") (pintype "passive"))
      (node (ref "R2") (pin "2") (pinfunction "2_2") (pintype "passive"))
    )
    (net (code "73") (name "Net-(OK1-A)") (class "Default")
      (node (ref "OK1") (pin "1") (pinfunction "A_1") (pintype "passive"))
      (node (ref "R22") (pin "2") (pinfunction "2_2") (pintype "passive"))
    )
    (net (code "74") (name "Net-(OK1-EMIT)") (class "Default")
      (node (ref "OK1") (pin "3") (pinfunction "EMIT_3") (pintype "passive"))
      (node (ref "R18") (pin "2") (pinfunction "2_2") (pintype "passive"))
    )
    (net (code "75") (name "Net-(OK2-A)") (class "Default")
      (node (ref "OK2") (pin "1") (pinfunction "A_1") (pintype "passive"))
      (node (ref "R23") (pin "2") (pinfunction "2_2") (pintype "passive"))
    )
    (net (code "76") (name "Net-(OK2-EMIT)") (class "Default")
      (node (ref "OK2") (pin "3") (pinfunction "EMIT_3") (pintype "passive"))
      (node (ref "R10") (pin "2") (pinfunction "2_2") (pintype "passive"))
    )
    (net (code "77") (name "Net-(OK3-A)") (class "Default")
      (node (ref "OK3") (pin "1") (pinfunction "A_1") (pintype "passive"))
      (node (ref "R24") (pin "2") (pinfunction "2_2") (pintype "passive"))
    )
    (net (code "78") (name "Net-(OK3-EMIT)") (class "Default")
      (node (ref "OK3") (pin "3") (pinfunction "EMIT_3") (pintype "passive"))
      (node (ref "R19") (pin "2") (pinfunction "2_2") (pintype "passive"))
    )
    (net (code "79") (name "Net-(OK4-A)") (class "Default")
      (node (ref "OK4") (pin "1") (pinfunction "A_1") (pintype "passive"))
      (node (ref "R31") (pin "2") (pinfunction "2_2") (pintype "passive"))
    )
    (net (code "80") (name "Net-(OK4-EMIT)") (class "Default")
      (node (ref "OK4") (pin "3") (pinfunction "EMIT_3") (pintype "passive"))
      (node (ref "R21") (pin "2") (pinfunction "2_2") (pintype "passive"))
    )
    (net (code "81") (name "Net-(Q1-B)") (class "Default")
      (node (ref "Q1") (pin "1") (pinfunction "B_1") (pintype "passive"))
      (node (ref "R18") (pin "1") (pinfunction "1_1") (pintype "passive"))
    )
    (net (code "82") (name "Net-(Q1-C)") (class "Default")
      (node (ref "K1") (pin "2") (pinfunction "2_2") (pintype "passive"))
      (node (ref "Q1") (pin "3") (pinfunction "C_3") (pintype "passive"))
    )
    (net (code "83") (name "Net-(Q2-B)") (class "Default")
      (node (ref "Q2") (pin "1") (pinfunction "B_1") (pintype "passive"))
      (node (ref "R19") (pin "1") (pinfunction "1_1") (pintype "passive"))
    )
    (net (code "84") (name "Net-(Q2-C)") (class "Default")
      (node (ref "K2") (pin "2") (pinfunction "2_2") (pintype "passive"))
      (node (ref "Q2") (pin "3") (pinfunction "C_3") (pintype "passive"))
    )
    (net (code "85") (name "Net-(Q3-B)") (class "Default")
      (node (ref "Q3") (pin "1") (pinfunction "B_1") (pintype "passive"))
      (node (ref "R21") (pin "1") (pinfunction "1_1") (pintype "passive"))
    )
    (net (code "86") (name "Net-(Q3-C)") (class "Default")
      (node (ref "K3") (pin "2") (pinfunction "2_2") (pintype "passive"))
      (node (ref "Q3") (pin "3") (pinfunction "C_3") (pintype "passive"))
    )
    (net (code "87") (name "Net-(Q4-B)") (class "Default")
      (node (ref "Q4") (pin "1") (pinfunction "B_1") (pintype "passive"))
      (node (ref "R10") (pin "1") (pinfunction "1_1") (pintype "passive"))
    )
    (net (code "88") (name "Net-(Q4-C)") (class "Default")
      (node (ref "K4") (pin "2") (pinfunction "2_2") (pintype "passive"))
      (node (ref "Q4") (pin "3") (pinfunction "C_3") (pintype "passive"))
    )
    (net (code "89") (name "Net-(Q5-B)") (class "Default")
      (node (ref "Q5") (pin "1") (pinfunction "B_1") (pintype "passive"))
      (node (ref "R8") (pin "1") (pinfunction "1_1") (pintype "passive"))
    )
    (net (code "90") (name "Net-(Q6-B)") (class "Default")
      (node (ref "Q6") (pin "1") (pinfunction "B_1") (pintype "passive"))
      (node (ref "R9") (pin "1") (pinfunction "1_1") (pintype "passive"))
    )
    (net (code "91") (name "Net-(U3-X1)") (class "Default")
      (node (ref "32.768KHZ") (pin "2") (pinfunction "2_2") (pintype "passive"))
      (node (ref "U3") (pin "1") (pinfunction "X1_1") (pintype "bidirectional"))
    )
    (net (code "92") (name "Net-(U3-X2)") (class "Default")
      (node (ref "32.768KHZ") (pin "1") (pinfunction "1_1") (pintype "passive"))
      (node (ref "U3") (pin "2") (pinfunction "X2_2") (pintype "bidirectional"))
    )
    (net (code "93") (name "unconnected-(ANT1-NC-Pad32)") (class "Default")
      (node (ref "ANT1") (pin "32") (pinfunction "NC_32") (pintype "no_connect"))
    )
    (net (code "94") (name "unconnected-(FLASH_SW-Pad2)") (class "Default")
      (node (ref "FLASH_SW") (pin "2") (pinfunction "2_2") (pintype "passive"))
    )
    (net (code "95") (name "unconnected-(FLASH_SW-Pad4)") (class "Default")
      (node (ref "FLASH_SW") (pin "4") (pinfunction "4_4") (pintype "passive"))
    )
    (net (code "96") (name "unconnected-(ICTOUART-CHR0-Pad15)") (class "Default")
      (node (ref "ICTOUART") (pin "15") (pinfunction "CHR0_15") (pintype "output"))
    )
    (net (code "97") (name "unconnected-(ICTOUART-CHR1-Pad14)") (class "Default")
      (node (ref "ICTOUART") (pin "14") (pinfunction "CHR1_14") (pintype "output"))
    )
    (net (code "98") (name "unconnected-(ICTOUART-CHREN-Pad13)") (class "Default")
      (node (ref "ICTOUART") (pin "13") (pinfunction "CHREN_13") (pintype "output"))
    )
    (net (code "99") (name "unconnected-(ICTOUART-CTS-Pad23)") (class "Default")
      (node (ref "ICTOUART") (pin "23") (pinfunction "CTS_23") (pintype "input"))
    )
    (net (code "100") (name "unconnected-(ICTOUART-DCD-Pad1)") (class "Default")
      (node (ref "ICTOUART") (pin "1") (pinfunction "DCD_1") (pintype "input"))
    )
    (net (code "101") (name "unconnected-(ICTOUART-DSR-Pad27)") (class "Default")
      (node (ref "ICTOUART") (pin "27") (pinfunction "DSR_27") (pintype "input"))
    )
    (net (code "102") (name "unconnected-(ICTOUART-GPIO.0{slash}TXT-Pad19)") (class "Default")
      (node (ref "ICTOUART") (pin "19") (pinfunction "GPIO.0/TXT_19") (pintype "bidirectional"))
    )
    (net (code "103") (name "unconnected-(ICTOUART-GPIO.1{slash}RXT-Pad18)") (class "Default")
      (node (ref "ICTOUART") (pin "18") (pinfunction "GPIO.1/RXT_18") (pintype "bidirectional"))
    )
    (net (code "104") (name "unconnected-(ICTOUART-GPIO.2{slash}RS485-Pad17)") (class "Default")
      (node (ref "ICTOUART") (pin "17") (pinfunction "GPIO.2/RS485_17") (pintype "bidirectional"))
    )
    (net (code "105") (name "unconnected-(ICTOUART-GPIO.3{slash}WAKEUP-Pad16)") (class "Default")
      (node (ref "ICTOUART") (pin "16") (pinfunction "GPIO.3/WAKEUP_16") (pintype "bidirectional"))
    )
    (net (code "106") (name "unconnected-(ICTOUART-GPIO.4-Pad22)") (class "Default")
      (node (ref "ICTOUART") (pin "22") (pinfunction "GPIO.4_22") (pintype "bidirectional"))
    )
    (net (code "107") (name "unconnected-(ICTOUART-GPIO.5-Pad21)") (class "Default")
      (node (ref "ICTOUART") (pin "21") (pinfunction "GPIO.5_21") (pintype "bidirectional"))
    )
    (net (code "108") (name "unconnected-(ICTOUART-GPIO.6-Pad20)") (class "Default")
      (node (ref "ICTOUART") (pin "20") (pinfunction "GPIO.6_20") (pintype "bidirectional"))
    )
    (net (code "109") (name "unconnected-(ICTOUART-RI{slash}CLK-Pad2)") (class "Default")
      (node (ref "ICTOUART") (pin "2") (pinfunction "RI/CLK_2") (pintype "bidirectional"))
    )
    (net (code "110") (name "unconnected-(ICTOUART-SUSPEND-Pad12)") (class "Default")
      (node (ref "ICTOUART") (pin "12") (pinfunction "SUSPEND_12") (pintype "output"))
    )
    (net (code "111") (name "unconnected-(IO2_SW-Pad2)") (class "Default")
      (node (ref "IO2_SW") (pin "2") (pinfunction "2_2") (pintype "passive"))
    )
    (net (code "112") (name "unconnected-(IO2_SW-Pad4)") (class "Default")
      (node (ref "IO2_SW") (pin "4") (pinfunction "4_4") (pintype "passive"))
    )
    (net (code "113") (name "unconnected-(IO11_SW-Pad2)") (class "Default")
      (node (ref "IO11_SW") (pin "2") (pinfunction "2_2") (pintype "passive"))
    )
    (net (code "114") (name "unconnected-(IO11_SW-Pad4)") (class "Default")
      (node (ref "IO11_SW") (pin "4") (pinfunction "4_4") (pintype "passive"))
    )
    (net (code "115") (name "unconnected-(J2-CTS-Pad5)") (class "Default")
      (node (ref "J2") (pin "5") (pinfunction "CTS_5") (pintype "passive"))
    )
    (net (code "116") (name "unconnected-(J2-DTR-Pad1)") (class "Default")
      (node (ref "J2") (pin "1") (pinfunction "DTR_1") (pintype "passive"))
    )
    (net (code "117") (name "unconnected-(RESET_SW-Pad2)") (class "Default")
      (node (ref "RESET_SW") (pin "2") (pinfunction "2_2") (pintype "passive"))
    )
    (net (code "118") (name "unconnected-(RESET_SW-Pad4)") (class "Default")
      (node (ref "RESET_SW") (pin "4") (pinfunction "4_4") (pintype "passive"))
    )
    (net (code "119") (name "unconnected-(U3-SQW-Pad7)") (class "Default")
      (node (ref "U3") (pin "7") (pinfunction "SQW_7") (pintype "bidirectional"))
    )
    (net (code "120") (name "unconnected-(USB-ID-Pad4)") (class "Default")
      (node (ref "USB") (pin "4") (pinfunction "ID_4") (pintype "bidirectional"))
    )
  )
)
